# 1-Schematic_Nakuja_Remix_3.net
KiCad netlist of a schematic drawn in EasyEDA
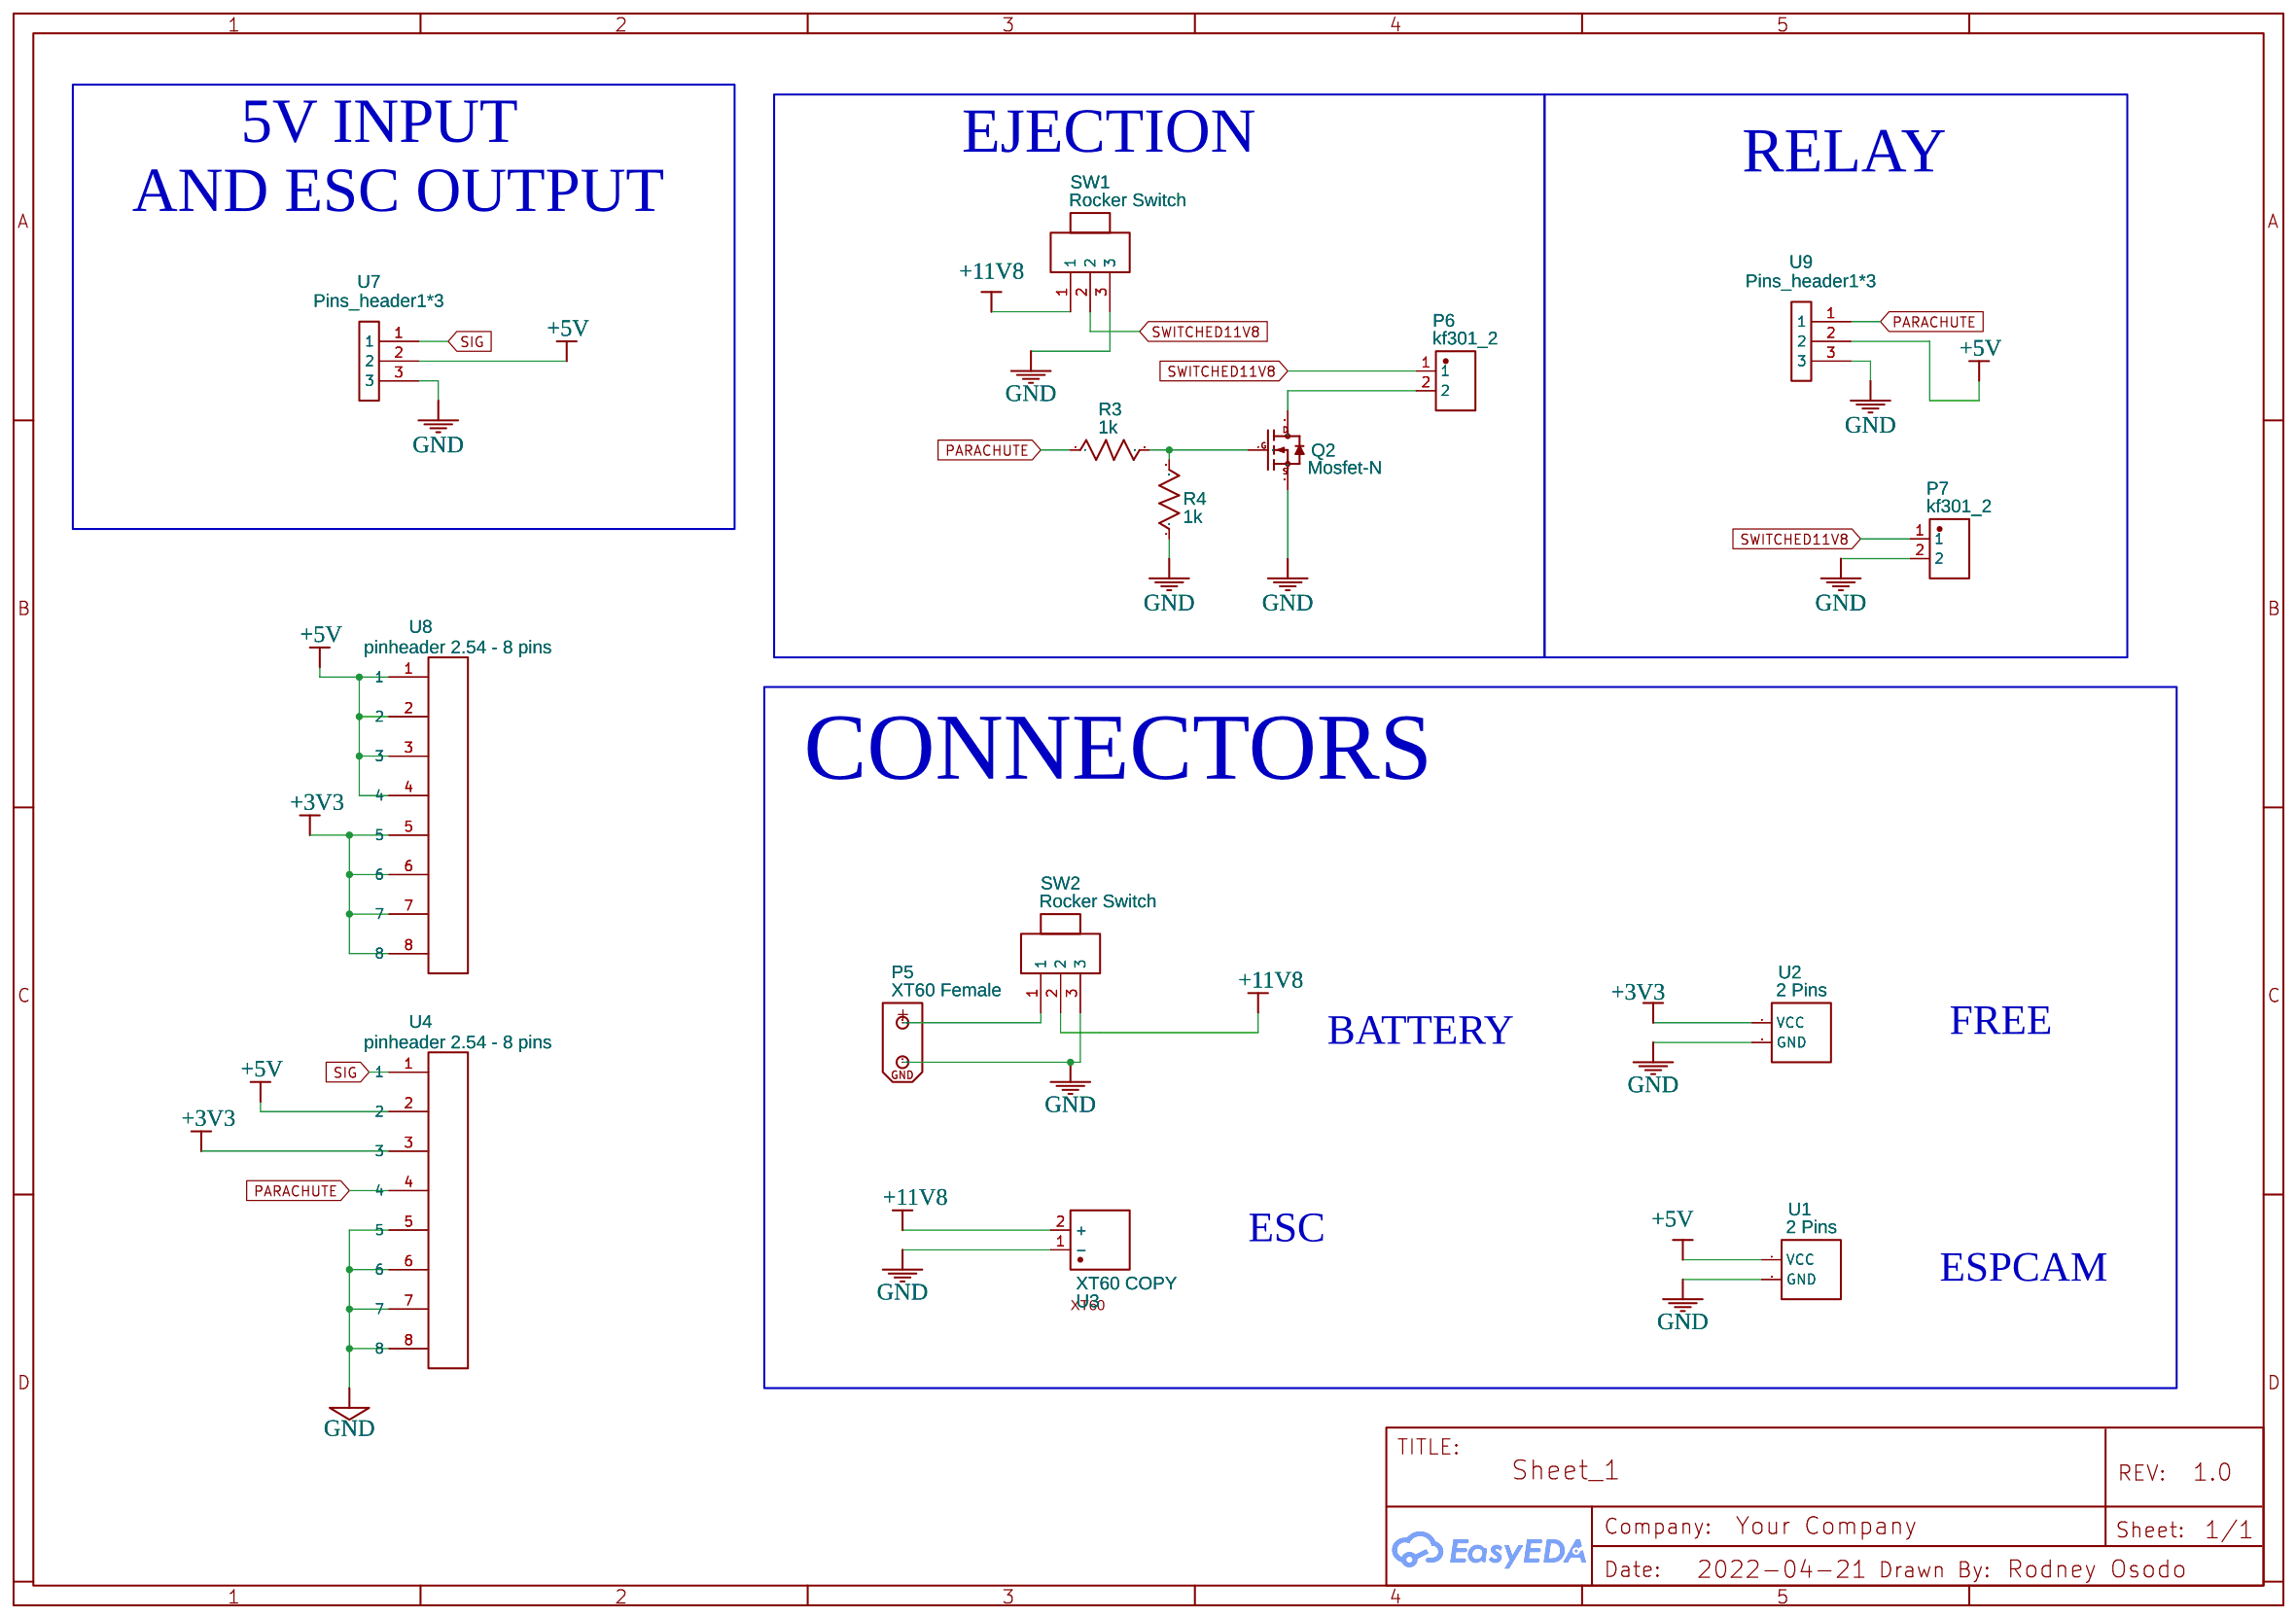
[diagram p0: schematic sheet]

(export (version "E")
  (design (tool "Eeschema 10.0.6"))
  (components
    (comp (ref "P5")
      (value "XT60 Female")
      (fields (field (name "BOM_Manufacturer Part") "XT60-F"))
      (libsource (lib "") (part "XT60 Female"))
    )
    (comp (ref "P6")
      (value "kf301_2")
      (fields (field (name "BOM_Supplier Part") "C33435"))
      (libsource (lib "") (part "kf301_2"))
    )
    (comp (ref "P7")
      (value "kf301_2")
      (fields (field (name "BOM_Supplier Part") "C33435"))
      (libsource (lib "") (part "kf301_2"))
    )
    (comp (ref "Q2") (value "Mosfet-N") (libsource (lib "") (part "Mosfet-N")))
    (comp (ref "R3") (value "1k") (libsource (lib "") (part "R_AXIAL-0.6_US_1")))
    (comp (ref "R4") (value "1k") (libsource (lib "") (part "R_AXIAL-0.6_US")))
    (comp (ref "SW1") (value "Rocker Switch") (libsource (lib "") (part "Rocker Switch")))
    (comp (ref "SW2") (value "Rocker Switch") (libsource (lib "") (part "Rocker Switch")))
    (comp (ref "U1") (value "2 Pins") (libsource (lib "") (part "2 Pins")))
    (comp (ref "U2") (value "2 Pins") (libsource (lib "") (part "2 Pins")))
    (comp (ref "U3") (value "XT60 COPY") (libsource (lib "") (part "XT60 COPY")))
    (comp (ref "U4") (value "pinheader 2.54 - 8 pins") (libsource (lib "") (part "pinheader 2.54 - 8 pins")))
    (comp (ref "U7") (value "Pins_header1*3") (libsource (lib "") (part "Pins_header1*3")))
    (comp (ref "U8") (value "pinheader 2.54 - 8 pins") (libsource (lib "") (part "pinheader 2.54 - 8 pins")))
    (comp (ref "U9") (value "Pins_header1*3") (libsource (lib "") (part "Pins_header1*3")))
  )
  (nets
    (net (code "1") (name "+3V3") (class "Default")
      (node (ref "U2") (pin "1") (pinfunction "VCC_1") (pintype "unspecified"))
      (node (ref "U4") (pin "3") (pinfunction "3_3") (pintype "unspecified"))
      (node (ref "U8") (pin "5") (pinfunction "5_5") (pintype "unspecified"))
      (node (ref "U8") (pin "6") (pinfunction "6_6") (pintype "unspecified"))
      (node (ref "U8") (pin "7") (pinfunction "7_7") (pintype "unspecified"))
      (node (ref "U8") (pin "8") (pinfunction "8_8") (pintype "unspecified"))
    )
    (net (code "2") (name "+5V") (class "Default")
      (node (ref "U1") (pin "1") (pinfunction "VCC_1") (pintype "unspecified"))
      (node (ref "U4") (pin "2") (pinfunction "2_2") (pintype "unspecified"))
      (node (ref "U7") (pin "2") (pinfunction "2_2") (pintype "unspecified"))
      (node (ref "U8") (pin "1") (pinfunction "1_1") (pintype "unspecified"))
      (node (ref "U8") (pin "2") (pinfunction "2_2") (pintype "unspecified"))
      (node (ref "U8") (pin "3") (pinfunction "3_3") (pintype "unspecified"))
      (node (ref "U8") (pin "4") (pinfunction "4_4") (pintype "unspecified"))
      (node (ref "U9") (pin "2") (pinfunction "2_2") (pintype "unspecified"))
    )
    (net (code "3") (name "+11V8") (class "Default")
      (node (ref "SW1") (pin "1") (pinfunction "1_1") (pintype "unspecified"))
      (node (ref "SW2") (pin "2") (pinfunction "2_2") (pintype "unspecified"))
      (node (ref "U3") (pin "2") (pinfunction "+_2") (pintype "unspecified"))
    )
    (net (code "4") (name "GND") (class "Default")
      (node (ref "P5") (pin "1") (pinfunction "1_1") (pintype "unspecified"))
      (node (ref "P7") (pin "2") (pinfunction "2_2") (pintype "unspecified"))
      (node (ref "Q2") (pin "3") (pinfunction "S_3") (pintype "unspecified"))
      (node (ref "R4") (pin "1") (pinfunction "1_1") (pintype "unspecified"))
      (node (ref "SW1") (pin "3") (pinfunction "3_3") (pintype "unspecified"))
      (node (ref "SW2") (pin "3") (pinfunction "3_3") (pintype "unspecified"))
      (node (ref "U1") (pin "2") (pinfunction "GND_2") (pintype "unspecified"))
      (node (ref "U2") (pin "2") (pinfunction "GND_2") (pintype "unspecified"))
      (node (ref "U3") (pin "1") (pinfunction "-_1") (pintype "unspecified"))
      (node (ref "U4") (pin "5") (pinfunction "5_5") (pintype "unspecified"))
      (node (ref "U4") (pin "6") (pinfunction "6_6") (pintype "unspecified"))
      (node (ref "U4") (pin "7") (pinfunction "7_7") (pintype "unspecified"))
      (node (ref "U4") (pin "8") (pinfunction "8_8") (pintype "unspecified"))
      (node (ref "U7") (pin "3") (pinfunction "3_3") (pintype "unspecified"))
      (node (ref "U9") (pin "3") (pinfunction "3_3") (pintype "unspecified"))
    )
    (net (code "5") (name "Net-(P5-Pad2)") (class "Default")
      (node (ref "P5") (pin "2") (pinfunction "2_2") (pintype "unspecified"))
      (node (ref "SW2") (pin "1") (pinfunction "1_1") (pintype "unspecified"))
    )
    (net (code "6") (name "Net-(Q2-D)") (class "Default")
      (node (ref "P6") (pin "2") (pinfunction "2_2") (pintype "unspecified"))
      (node (ref "Q2") (pin "2") (pinfunction "D_2") (pintype "unspecified"))
    )
    (net (code "7") (name "Net-(Q2-G)") (class "Default")
      (node (ref "Q2") (pin "1") (pinfunction "G_1") (pintype "unspecified"))
      (node (ref "R3") (pin "2") (pinfunction "2_2") (pintype "unspecified"))
      (node (ref "R4") (pin "2") (pinfunction "2_2") (pintype "unspecified"))
    )
    (net (code "8") (name "PARACHUTE") (class "Default")
      (node (ref "R3") (pin "1") (pinfunction "1_1") (pintype "unspecified"))
      (node (ref "U4") (pin "4") (pinfunction "4_4") (pintype "unspecified"))
      (node (ref "U9") (pin "1") (pinfunction "1_1") (pintype "unspecified"))
    )
    (net (code "9") (name "SIG") (class "Default")
      (node (ref "U4") (pin "1") (pinfunction "1_1") (pintype "unspecified"))
      (node (ref "U7") (pin "1") (pinfunction "1_1") (pintype "unspecified"))
    )
    (net (code "10") (name "SWITCHED11V8") (class "Default")
      (node (ref "P6") (pin "1") (pinfunction "1_1") (pintype "unspecified"))
      (node (ref "P7") (pin "1") (pinfunction "1_1") (pintype "unspecified"))
      (node (ref "SW1") (pin "2") (pinfunction "2_2") (pintype "unspecified"))
    )
  )
)
